# DI_DO.net
KiCad netlist of a schematic drawn in Altium Designer
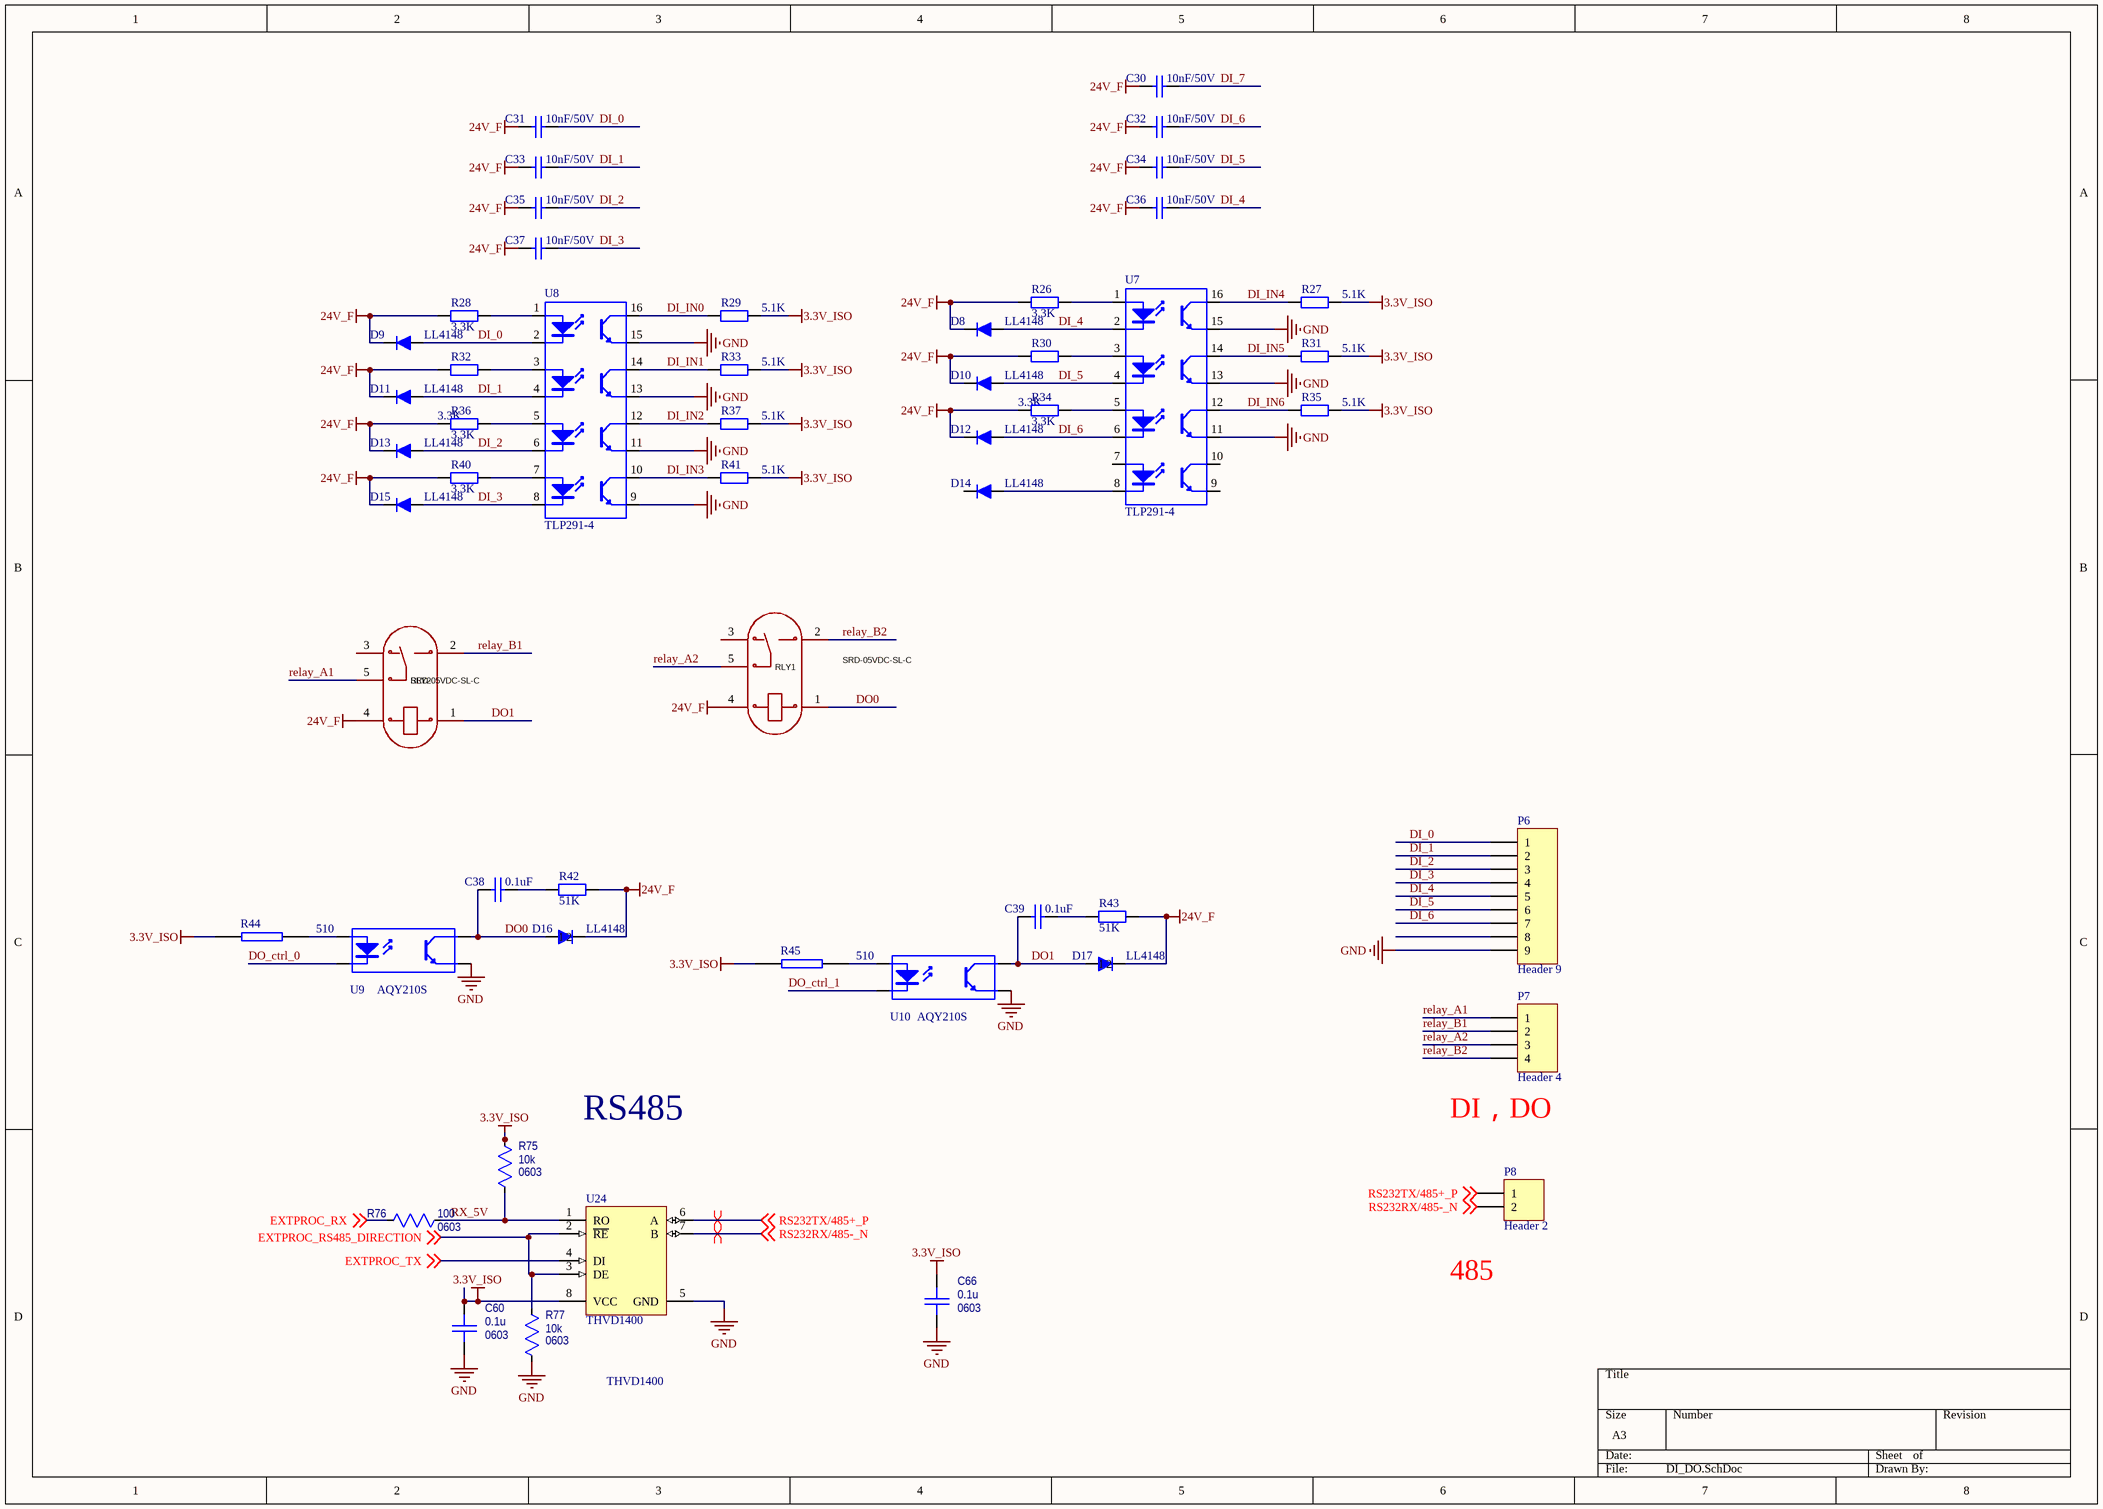
[diagram p0: DI_DO.SchDoc]

(export (version "E")
  (design (tool "Eeschema 10.0.6"))
  (components
    (comp (ref "C30")
      (value "10nF/50V")
      (footprint "0603C")
      (description "Capacitor")
      (fields (field (name "PUBLISHER") "Altium Limited"))
      (libsource (lib "Miscellaneous Devices") (part "Cap"))
    )
    (comp (ref "C31")
      (value "10nF/50V")
      (footprint "0603C")
      (description "Capacitor")
      (fields (field (name "PUBLISHER") "Altium Limited"))
      (libsource (lib "Miscellaneous Devices") (part "Cap"))
    )
    (comp (ref "C32")
      (value "10nF/50V")
      (footprint "0603C")
      (description "Capacitor")
      (fields (field (name "PUBLISHER") "Altium Limited"))
      (libsource (lib "Miscellaneous Devices") (part "Cap"))
    )
    (comp (ref "C33")
      (value "10nF/50V")
      (footprint "0603C")
      (description "Capacitor")
      (fields (field (name "PUBLISHER") "Altium Limited"))
      (libsource (lib "Miscellaneous Devices") (part "Cap"))
    )
    (comp (ref "C34")
      (value "10nF/50V")
      (footprint "0603C")
      (description "Capacitor")
      (fields (field (name "PUBLISHER") "Altium Limited"))
      (libsource (lib "Miscellaneous Devices") (part "Cap"))
    )
    (comp (ref "C35")
      (value "10nF/50V")
      (footprint "0603C")
      (description "Capacitor")
      (fields (field (name "PUBLISHER") "Altium Limited"))
      (libsource (lib "Miscellaneous Devices") (part "Cap"))
    )
    (comp (ref "C36")
      (value "10nF/50V")
      (footprint "0603C")
      (description "Capacitor")
      (fields (field (name "PUBLISHER") "Altium Limited"))
      (libsource (lib "Miscellaneous Devices") (part "Cap"))
    )
    (comp (ref "C37")
      (value "10nF/50V")
      (footprint "0603C")
      (description "Capacitor")
      (fields (field (name "PUBLISHER") "Altium Limited"))
      (libsource (lib "Miscellaneous Devices") (part "Cap"))
    )
    (comp (ref "C38")
      (value "0.1uF")
      (footprint "0603C")
      (description "Capacitor")
      (libsource (lib "*") (part "CAP"))
    )
    (comp (ref "C39")
      (value "0.1uF")
      (footprint "0603C")
      (description "Capacitor")
      (libsource (lib "*") (part "CAP"))
    )
    (comp (ref "C60")
      (value "0.1u")
      (footprint "CAPC1608X092N_0603")
      (description "Capacitor, MLCC")
      (fields
        (field (name "PARTNUMBER") "C0603C104M5RACTU")
        (field (name "TOLERANCE") "[tol]")
        (field (name "PACKAGE") "0603")
      )
      (libsource (lib "Karl") (part "Capacitor_0603"))
    )
    (comp (ref "C66")
      (value "0.1u")
      (footprint "CAPC1608X092N_0603")
      (description "Capacitor, MLCC")
      (fields
        (field (name "PARTNUMBER") "C0603C104M5RACTU")
        (field (name "TOLERANCE") "[tol]")
        (field (name "PACKAGE") "0603")
      )
      (libsource (lib "Karl") (part "Capacitor_0603"))
    )
    (comp (ref "D8")
      (value "LL4148")
      (footprint "DO-213AB/LL34/MiniMELF")
      (description "VISHAY,LL4148,圆柱体MiniMELF100V/2A,ROHS")
      (libsource (lib "Device2018") (part "LL4148"))
    )
    (comp (ref "D9")
      (value "LL4148")
      (footprint "DO-213AB/LL34/MiniMELF")
      (description "VISHAY,LL4148,圆柱体MiniMELF100V/2A,ROHS")
      (libsource (lib "Device2018") (part "LL4148"))
    )
    (comp (ref "D10")
      (value "LL4148")
      (footprint "DO-213AB/LL34/MiniMELF")
      (description "VISHAY,LL4148,圆柱体MiniMELF100V/2A,ROHS")
      (libsource (lib "Device2018") (part "LL4148"))
    )
    (comp (ref "D11")
      (value "LL4148")
      (footprint "DO-213AB/LL34/MiniMELF")
      (description "VISHAY,LL4148,圆柱体MiniMELF100V/2A,ROHS")
      (libsource (lib "Device2018") (part "LL4148"))
    )
    (comp (ref "D12")
      (value "LL4148")
      (footprint "DO-213AB/LL34/MiniMELF")
      (description "VISHAY,LL4148,圆柱体MiniMELF100V/2A,ROHS")
      (libsource (lib "Device2018") (part "LL4148"))
    )
    (comp (ref "D13")
      (value "LL4148")
      (footprint "DO-213AB/LL34/MiniMELF")
      (description "VISHAY,LL4148,圆柱体MiniMELF100V/2A,ROHS")
      (libsource (lib "Device2018") (part "LL4148"))
    )
    (comp (ref "D14")
      (value "LL4148")
      (footprint "DO-213AB/LL34/MiniMELF")
      (description "VISHAY,LL4148,圆柱体MiniMELF100V/2A,ROHS")
      (libsource (lib "Device2018") (part "LL4148"))
    )
    (comp (ref "D15")
      (value "LL4148")
      (footprint "DO-213AB/LL34/MiniMELF")
      (description "VISHAY,LL4148,圆柱体MiniMELF100V/2A,ROHS")
      (libsource (lib "Device2018") (part "LL4148"))
    )
    (comp (ref "D16")
      (value "LL4148")
      (footprint "DO-213AB/LL34/MiniMELF")
      (description "VISHAY,LL4148,圆柱体MiniMELF100V/2A,ROHS")
      (libsource (lib "") (part "LL4148_1"))
    )
    (comp (ref "D17")
      (value "LL4148")
      (footprint "DO-213AB/LL34/MiniMELF")
      (description "VISHAY,LL4148,圆柱体MiniMELF100V/2A,ROHS")
      (libsource (lib "") (part "LL4148_1"))
    )
    (comp (ref "P6")
      (value "Header 9")
      (footprint "HDR1X9")
      (description "Header, 9-Pin")
      (fields (field (name "PUBLISHER") "Altium Limited"))
      (libsource (lib "Miscellaneous Connectors") (part "Header 9"))
    )
    (comp (ref "P7")
      (value "Header 4")
      (footprint "HDR1X4")
      (description "Header, 4-Pin")
      (fields (field (name "PUBLISHER") "Altium Limited"))
      (libsource (lib "Miscellaneous Connectors") (part "Header 4"))
    )
    (comp (ref "P8")
      (value "Header 2")
      (footprint "HDR1X2")
      (description "Header, 2-Pin")
      (fields (field (name "PUBLISHER") "Altium Limited"))
      (libsource (lib "Miscellaneous Connectors") (part "Header 2"))
    )
    (comp (ref "R26") (value "3.3K") (footprint "0603R") (libsource (lib "MQlibrary") (part "Res0805M")))
    (comp (ref "R27") (value "5.1K") (footprint "0603R") (libsource (lib "MQlibrary") (part "Res0805M")))
    (comp (ref "R28") (value "3.3K") (footprint "0603R") (libsource (lib "MQlibrary") (part "Res0805M")))
    (comp (ref "R29") (value "5.1K") (footprint "0603R") (libsource (lib "MQlibrary") (part "Res0805M")))
    (comp (ref "R30") (value "3.3K") (footprint "0603R") (libsource (lib "MQlibrary") (part "Res0805M")))
    (comp (ref "R31") (value "5.1K") (footprint "0603R") (libsource (lib "MQlibrary") (part "Res0805M")))
    (comp (ref "R32") (value "3.3K") (footprint "0603R") (libsource (lib "MQlibrary") (part "Res0805M")))
    (comp (ref "R33") (value "5.1K") (footprint "0603R") (libsource (lib "MQlibrary") (part "Res0805M")))
    (comp (ref "R34") (value "3.3K") (footprint "0603R") (libsource (lib "MQlibrary") (part "Res0805M")))
    (comp (ref "R35") (value "5.1K") (footprint "0603R") (libsource (lib "MQlibrary") (part "Res0805M")))
    (comp (ref "R36") (value "3.3K") (footprint "0603R") (libsource (lib "MQlibrary") (part "Res0805M")))
    (comp (ref "R37") (value "5.1K") (footprint "0603R") (libsource (lib "MQlibrary") (part "Res0805M")))
    (comp (ref "R40") (value "3.3K") (footprint "0603R") (libsource (lib "MQlibrary") (part "Res0805M")))
    (comp (ref "R41") (value "5.1K") (footprint "0603R") (libsource (lib "MQlibrary") (part "Res0805M")))
    (comp (ref "R42") (value "51K") (footprint "0603R") (libsource (lib "") (part "Res0805M_1")))
    (comp (ref "R43") (value "51K") (footprint "0603R") (libsource (lib "") (part "Res0805M_1")))
    (comp (ref "R44") (value "510") (footprint "0603R") (libsource (lib "*") (part "RES2")))
    (comp (ref "R45") (value "510") (footprint "0603R") (libsource (lib "*") (part "RES2")))
    (comp (ref "R75")
      (value "10k")
      (footprint "RESC1608X055N_0603")
      (description "Resistor, Standard")
      (fields
        (field (name "PARTNUMBER") "RC0603FR-0710KL")
        (field (name "TOLERANCE") "tol")
        (field (name "PACKAGE") "0603")
      )
      (libsource (lib "Karl") (part "Resistor_0603"))
    )
    (comp (ref "R76")
      (value "100")
      (footprint "RESC1608X055N_0603")
      (description "Resistor, Standard")
      (fields
        (field (name "PARTNUMBER") "RC0603FR-07100RL")
        (field (name "TOLERANCE") "tol")
        (field (name "PACKAGE") "0603")
      )
      (libsource (lib "Karl") (part "Resistor_0603"))
    )
    (comp (ref "R77")
      (value "10k")
      (footprint "RESC1608X055N_0603")
      (description "Resistor, Standard")
      (fields
        (field (name "PARTNUMBER") "RC0603FR-0710KL")
        (field (name "TOLERANCE") "tol")
        (field (name "PACKAGE") "0603")
      )
      (libsource (lib "Karl") (part "Resistor_0603"))
    )
    (comp (ref "RLY1")
      (value "SRD-05VDC-SL-C")
      (footprint "RELAY-TH_SRD-XXVDC-XL-C")
      (fields (field (name "MANUFACTURER") "松乐"))
      (libsource (lib "altium-import") (part "root_0_SRD-05VDC-SL-C_"))
    )
    (comp (ref "RLY2")
      (value "SRD-05VDC-SL-C")
      (footprint "RELAY-TH_SRD-XXVDC-XL-C")
      (fields (field (name "MANUFACTURER") "松乐"))
      (libsource (lib "altium-import") (part "root_0_SRD-05VDC-SL-C_"))
    )
    (comp (ref "U7") (value "TLP291-4") (footprint "SOP16-T") (libsource (lib "DI16") (part "TLP281-4")))
    (comp (ref "U8") (value "TLP291-4") (footprint "SOP16-T") (libsource (lib "DI16") (part "TLP281-4")))
    (comp (ref "U9")
      (value "AQY210S")
      (footprint "sop4")
      (description "4-Pin Phototransistor Optocoupler")
      (fields (field (name "PUBLISHER") "Altium Limited"))
      (libsource (lib "Miscellaneous Devices") (part "Optoisolator1"))
    )
    (comp (ref "U10")
      (value "AQY210S")
      (footprint "sop4")
      (description "4-Pin Phototransistor Optocoupler")
      (fields (field (name "PUBLISHER") "Altium Limited"))
      (libsource (lib "Miscellaneous Devices") (part "Optoisolator1"))
    )
    (comp (ref "U24")
      (value "THVD1400")
      (footprint "MAXM-S8+4_M")
      (fields (field (name "PARTNUMBER") "MAX33071EASA+"))
      (libsource (lib "Bogen") (part "MAX33071EASA+"))
    )
  )
  (nets
    (net (code "1") (name "/DI_0") (class "Default")
      (node (ref "C31") (pin "2") (pinfunction "2_2") (pintype "passive"))
      (node (ref "D9") (pin "1") (pinfunction "2_1") (pintype "passive"))
      (node (ref "P6") (pin "1") (pinfunction "1_1") (pintype "passive"))
      (node (ref "U8") (pin "2") (pinfunction "K_2") (pintype "passive"))
    )
    (net (code "2") (name "/DI_1") (class "Default")
      (node (ref "C33") (pin "2") (pinfunction "2_2") (pintype "passive"))
      (node (ref "D11") (pin "1") (pinfunction "2_1") (pintype "passive"))
      (node (ref "P6") (pin "2") (pinfunction "2_2") (pintype "passive"))
      (node (ref "U8") (pin "4") (pinfunction "K_4") (pintype "passive"))
    )
    (net (code "3") (name "/DI_2") (class "Default")
      (node (ref "C35") (pin "2") (pinfunction "2_2") (pintype "passive"))
      (node (ref "D13") (pin "1") (pinfunction "2_1") (pintype "passive"))
      (node (ref "P6") (pin "3") (pinfunction "3_3") (pintype "passive"))
      (node (ref "U8") (pin "6") (pinfunction "K_6") (pintype "passive"))
    )
    (net (code "4") (name "/DI_3") (class "Default")
      (node (ref "C37") (pin "2") (pinfunction "2_2") (pintype "passive"))
      (node (ref "D15") (pin "1") (pinfunction "2_1") (pintype "passive"))
      (node (ref "P6") (pin "4") (pinfunction "4_4") (pintype "passive"))
      (node (ref "U8") (pin "8") (pinfunction "K_8") (pintype "passive"))
    )
    (net (code "5") (name "/DI_4") (class "Default")
      (node (ref "C36") (pin "2") (pinfunction "2_2") (pintype "passive"))
      (node (ref "D8") (pin "1") (pinfunction "2_1") (pintype "passive"))
      (node (ref "P6") (pin "5") (pinfunction "5_5") (pintype "passive"))
      (node (ref "U7") (pin "2") (pinfunction "K_2") (pintype "passive"))
    )
    (net (code "6") (name "/DI_5") (class "Default")
      (node (ref "C34") (pin "2") (pinfunction "2_2") (pintype "passive"))
      (node (ref "D10") (pin "1") (pinfunction "2_1") (pintype "passive"))
      (node (ref "P6") (pin "6") (pinfunction "6_6") (pintype "passive"))
      (node (ref "U7") (pin "4") (pinfunction "K_4") (pintype "passive"))
    )
    (net (code "7") (name "/DI_6") (class "Default")
      (node (ref "C32") (pin "2") (pinfunction "2_2") (pintype "passive"))
      (node (ref "D12") (pin "1") (pinfunction "2_1") (pintype "passive"))
      (node (ref "P6") (pin "7") (pinfunction "7_7") (pintype "passive"))
      (node (ref "U7") (pin "6") (pinfunction "K_6") (pintype "passive"))
    )
    (net (code "8") (name "/DI_7") (class "Default")
      (node (ref "C30") (pin "2") (pinfunction "2_2") (pintype "passive"))
    )
    (net (code "9") (name "/DI_IN0") (class "Default")
      (node (ref "R29") (pin "2") (pinfunction "2_2") (pintype "passive"))
      (node (ref "U8") (pin "16") (pinfunction "C_16") (pintype "passive"))
    )
    (net (code "10") (name "/DI_IN1") (class "Default")
      (node (ref "R33") (pin "2") (pinfunction "2_2") (pintype "passive"))
      (node (ref "U8") (pin "14") (pinfunction "C_14") (pintype "passive"))
    )
    (net (code "11") (name "/DI_IN2") (class "Default")
      (node (ref "R37") (pin "2") (pinfunction "2_2") (pintype "passive"))
      (node (ref "U8") (pin "12") (pinfunction "C_12") (pintype "passive"))
    )
    (net (code "12") (name "/DI_IN3") (class "Default")
      (node (ref "R41") (pin "2") (pinfunction "2_2") (pintype "passive"))
      (node (ref "U8") (pin "10") (pinfunction "C_10") (pintype "passive"))
    )
    (net (code "13") (name "/DI_IN4") (class "Default")
      (node (ref "R27") (pin "2") (pinfunction "2_2") (pintype "passive"))
      (node (ref "U7") (pin "16") (pinfunction "C_16") (pintype "passive"))
    )
    (net (code "14") (name "/DI_IN5") (class "Default")
      (node (ref "R31") (pin "2") (pinfunction "2_2") (pintype "passive"))
      (node (ref "U7") (pin "14") (pinfunction "C_14") (pintype "passive"))
    )
    (net (code "15") (name "/DI_IN6") (class "Default")
      (node (ref "R35") (pin "2") (pinfunction "2_2") (pintype "passive"))
      (node (ref "U7") (pin "12") (pinfunction "C_12") (pintype "passive"))
    )
    (net (code "16") (name "/DO0") (class "Default")
      (node (ref "C38") (pin "1") (pinfunction "1_1") (pintype "passive"))
      (node (ref "D16") (pin "1") (pinfunction "2_1") (pintype "passive"))
      (node (ref "RLY1") (pin "1") (pinfunction "1_1") (pintype "passive"))
      (node (ref "U9") (pin "4") (pinfunction "C_4") (pintype "passive"))
    )
    (net (code "17") (name "/DO1") (class "Default")
      (node (ref "C39") (pin "1") (pinfunction "1_1") (pintype "passive"))
      (node (ref "D17") (pin "1") (pinfunction "2_1") (pintype "passive"))
      (node (ref "RLY2") (pin "1") (pinfunction "1_1") (pintype "passive"))
      (node (ref "U10") (pin "4") (pinfunction "C_4") (pintype "passive"))
    )
    (net (code "18") (name "/DO_ctrl_0") (class "Default")
      (node (ref "U9") (pin "2") (pinfunction "K_2") (pintype "passive"))
    )
    (net (code "19") (name "/DO_ctrl_1") (class "Default")
      (node (ref "U10") (pin "2") (pinfunction "K_2") (pintype "passive"))
    )
    (net (code "20") (name "/RX_5V") (class "Default")
      (node (ref "R75") (pin "1") (pinfunction "1_1") (pintype "passive"))
      (node (ref "R76") (pin "1") (pinfunction "1_1") (pintype "passive"))
      (node (ref "U24") (pin "1") (pinfunction "RO_1") (pintype "tri_state"))
    )
    (net (code "21") (name "/relay_A1") (class "Default")
      (node (ref "P7") (pin "1") (pinfunction "1_1") (pintype "passive"))
      (node (ref "RLY2") (pin "5") (pinfunction "5_5") (pintype "passive"))
    )
    (net (code "22") (name "/relay_A2") (class "Default")
      (node (ref "P7") (pin "3") (pinfunction "3_3") (pintype "passive"))
      (node (ref "RLY1") (pin "5") (pinfunction "5_5") (pintype "passive"))
    )
    (net (code "23") (name "/relay_B1") (class "Default")
      (node (ref "P7") (pin "2") (pinfunction "2_2") (pintype "passive"))
      (node (ref "RLY2") (pin "2") (pinfunction "2_2") (pintype "passive"))
    )
    (net (code "24") (name "/relay_B2") (class "Default")
      (node (ref "P7") (pin "4") (pinfunction "4_4") (pintype "passive"))
      (node (ref "RLY1") (pin "2") (pinfunction "2_2") (pintype "passive"))
    )
    (net (code "25") (name "3.3V_ISO") (class "Default")
      (node (ref "C60") (pin "1") (pinfunction "1_1") (pintype "passive"))
      (node (ref "C66") (pin "1") (pinfunction "1_1") (pintype "passive"))
      (node (ref "R27") (pin "1") (pinfunction "1_1") (pintype "passive"))
      (node (ref "R29") (pin "1") (pinfunction "1_1") (pintype "passive"))
      (node (ref "R31") (pin "1") (pinfunction "1_1") (pintype "passive"))
      (node (ref "R33") (pin "1") (pinfunction "1_1") (pintype "passive"))
      (node (ref "R35") (pin "1") (pinfunction "1_1") (pintype "passive"))
      (node (ref "R37") (pin "1") (pinfunction "1_1") (pintype "passive"))
      (node (ref "R41") (pin "1") (pinfunction "1_1") (pintype "passive"))
      (node (ref "R44") (pin "2") (pinfunction "2_2") (pintype "passive"))
      (node (ref "R45") (pin "2") (pinfunction "2_2") (pintype "passive"))
      (node (ref "R75") (pin "2") (pinfunction "2_2") (pintype "passive"))
      (node (ref "U24") (pin "8") (pinfunction "VCC_8") (pintype "power_in"))
    )
    (net (code "26") (name "24V_F") (class "Default")
      (node (ref "C30") (pin "1") (pinfunction "1_1") (pintype "passive"))
      (node (ref "C31") (pin "1") (pinfunction "1_1") (pintype "passive"))
      (node (ref "C32") (pin "1") (pinfunction "1_1") (pintype "passive"))
      (node (ref "C33") (pin "1") (pinfunction "1_1") (pintype "passive"))
      (node (ref "C34") (pin "1") (pinfunction "1_1") (pintype "passive"))
      (node (ref "C35") (pin "1") (pinfunction "1_1") (pintype "passive"))
      (node (ref "C36") (pin "1") (pinfunction "1_1") (pintype "passive"))
      (node (ref "C37") (pin "1") (pinfunction "1_1") (pintype "passive"))
      (node (ref "D10") (pin "2") (pinfunction "1_2") (pintype "passive"))
      (node (ref "D11") (pin "2") (pinfunction "1_2") (pintype "passive"))
      (node (ref "D12") (pin "2") (pinfunction "1_2") (pintype "passive"))
      (node (ref "D13") (pin "2") (pinfunction "1_2") (pintype "passive"))
      (node (ref "D15") (pin "2") (pinfunction "1_2") (pintype "passive"))
      (node (ref "D16") (pin "2") (pinfunction "1_2") (pintype "passive"))
      (node (ref "D17") (pin "2") (pinfunction "1_2") (pintype "passive"))
      (node (ref "D8") (pin "2") (pinfunction "1_2") (pintype "passive"))
      (node (ref "D9") (pin "2") (pinfunction "1_2") (pintype "passive"))
      (node (ref "R26") (pin "2") (pinfunction "2_2") (pintype "passive"))
      (node (ref "R28") (pin "2") (pinfunction "2_2") (pintype "passive"))
      (node (ref "R30") (pin "2") (pinfunction "2_2") (pintype "passive"))
      (node (ref "R32") (pin "2") (pinfunction "2_2") (pintype "passive"))
      (node (ref "R34") (pin "2") (pinfunction "2_2") (pintype "passive"))
      (node (ref "R36") (pin "2") (pinfunction "2_2") (pintype "passive"))
      (node (ref "R40") (pin "2") (pinfunction "2_2") (pintype "passive"))
      (node (ref "R42") (pin "2") (pinfunction "2_2") (pintype "passive"))
      (node (ref "R43") (pin "2") (pinfunction "2_2") (pintype "passive"))
      (node (ref "RLY1") (pin "4") (pinfunction "4_4") (pintype "passive"))
      (node (ref "RLY2") (pin "4") (pinfunction "4_4") (pintype "passive"))
    )
    (net (code "27") (name "EXTPROC_RS485_DIRECTION") (class "Default")
      (node (ref "R77") (pin "2") (pinfunction "2_2") (pintype "passive"))
      (node (ref "U24") (pin "2") (pinfunction "~{RE}_2") (pintype "input"))
      (node (ref "U24") (pin "3") (pinfunction "DE_3") (pintype "input"))
    )
    (net (code "28") (name "EXTPROC_RX") (class "Default")
      (node (ref "R76") (pin "2") (pinfunction "2_2") (pintype "passive"))
    )
    (net (code "29") (name "EXTPROC_TX") (class "Default")
      (node (ref "U24") (pin "4") (pinfunction "DI_4") (pintype "input"))
    )
    (net (code "30") (name "GND") (class "Default")
      (node (ref "C60") (pin "2") (pinfunction "2_2") (pintype "passive"))
      (node (ref "C66") (pin "2") (pinfunction "2_2") (pintype "passive"))
      (node (ref "P6") (pin "9") (pinfunction "9_9") (pintype "passive"))
      (node (ref "R77") (pin "1") (pinfunction "1_1") (pintype "passive"))
      (node (ref "U10") (pin "3") (pinfunction "E_3") (pintype "passive"))
      (node (ref "U24") (pin "5") (pinfunction "GND_5") (pintype "power_in"))
      (node (ref "U7") (pin "11") (pinfunction "E_11") (pintype "passive"))
      (node (ref "U7") (pin "13") (pinfunction "E_13") (pintype "passive"))
      (node (ref "U7") (pin "15") (pinfunction "E_15") (pintype "passive"))
      (node (ref "U8") (pin "11") (pinfunction "E_11") (pintype "passive"))
      (node (ref "U8") (pin "13") (pinfunction "E_13") (pintype "passive"))
      (node (ref "U8") (pin "15") (pinfunction "E_15") (pintype "passive"))
      (node (ref "U8") (pin "9") (pinfunction "E_9") (pintype "passive"))
      (node (ref "U9") (pin "3") (pinfunction "E_3") (pintype "passive"))
    )
    (net (code "31") (name "Net-(C38-Pad2)") (class "Default")
      (node (ref "C38") (pin "2") (pinfunction "2_2") (pintype "passive"))
      (node (ref "R42") (pin "1") (pinfunction "1_1") (pintype "passive"))
    )
    (net (code "32") (name "Net-(C39-Pad2)") (class "Default")
      (node (ref "C39") (pin "2") (pinfunction "2_2") (pintype "passive"))
      (node (ref "R43") (pin "1") (pinfunction "1_1") (pintype "passive"))
    )
    (net (code "33") (name "Net-(D14-2)") (class "Default")
      (node (ref "D14") (pin "1") (pinfunction "2_1") (pintype "passive"))
      (node (ref "U7") (pin "8") (pinfunction "K_8") (pintype "passive"))
    )
    (net (code "34") (name "Net-(R26-Pad1)") (class "Default")
      (node (ref "R26") (pin "1") (pinfunction "1_1") (pintype "passive"))
      (node (ref "U7") (pin "1") (pinfunction "A_1") (pintype "passive"))
    )
    (net (code "35") (name "Net-(R28-Pad1)") (class "Default")
      (node (ref "R28") (pin "1") (pinfunction "1_1") (pintype "passive"))
      (node (ref "U8") (pin "1") (pinfunction "A_1") (pintype "passive"))
    )
    (net (code "36") (name "Net-(R30-Pad1)") (class "Default")
      (node (ref "R30") (pin "1") (pinfunction "1_1") (pintype "passive"))
      (node (ref "U7") (pin "3") (pinfunction "A_3") (pintype "passive"))
    )
    (net (code "37") (name "Net-(R32-Pad1)") (class "Default")
      (node (ref "R32") (pin "1") (pinfunction "1_1") (pintype "passive"))
      (node (ref "U8") (pin "3") (pinfunction "A_3") (pintype "passive"))
    )
    (net (code "38") (name "Net-(R34-Pad1)") (class "Default")
      (node (ref "R34") (pin "1") (pinfunction "1_1") (pintype "passive"))
      (node (ref "U7") (pin "5") (pinfunction "A_5") (pintype "passive"))
    )
    (net (code "39") (name "Net-(R36-Pad1)") (class "Default")
      (node (ref "R36") (pin "1") (pinfunction "1_1") (pintype "passive"))
      (node (ref "U8") (pin "5") (pinfunction "A_5") (pintype "passive"))
    )
    (net (code "40") (name "Net-(R40-Pad1)") (class "Default")
      (node (ref "R40") (pin "1") (pinfunction "1_1") (pintype "passive"))
      (node (ref "U8") (pin "7") (pinfunction "A_7") (pintype "passive"))
    )
    (net (code "41") (name "Net-(U9-A)") (class "Default")
      (node (ref "R44") (pin "1") (pinfunction "1_1") (pintype "passive"))
      (node (ref "U9") (pin "1") (pinfunction "A_1") (pintype "passive"))
    )
    (net (code "42") (name "Net-(U10-A)") (class "Default")
      (node (ref "R45") (pin "1") (pinfunction "1_1") (pintype "passive"))
      (node (ref "U10") (pin "1") (pinfunction "A_1") (pintype "passive"))
    )
    (net (code "43") (name "RS232RX{slash}485-_N") (class "Default")
      (node (ref "P8") (pin "2") (pinfunction "2_2") (pintype "passive"))
      (node (ref "U24") (pin "7") (pinfunction "B_7") (pintype "bidirectional"))
    )
    (net (code "44") (name "RS232TX{slash}485+_P") (class "Default")
      (node (ref "P8") (pin "1") (pinfunction "1_1") (pintype "passive"))
      (node (ref "U24") (pin "6") (pinfunction "A_6") (pintype "bidirectional"))
    )
    (net (code "45") (name "unconnected-(D14-1-Pad2)") (class "Default")
      (node (ref "D14") (pin "2") (pinfunction "1_2") (pintype "passive"))
    )
    (net (code "46") (name "unconnected-(P6-Pad8)") (class "Default")
      (node (ref "P6") (pin "8") (pinfunction "8_8") (pintype "passive"))
    )
    (net (code "47") (name "unconnected-(RLY1-Pad3)") (class "Default")
      (node (ref "RLY1") (pin "3") (pinfunction "3_3") (pintype "passive"))
    )
    (net (code "48") (name "unconnected-(RLY2-Pad3)") (class "Default")
      (node (ref "RLY2") (pin "3") (pinfunction "3_3") (pintype "passive"))
    )
    (net (code "49") (name "unconnected-(U7-A-Pad7)") (class "Default")
      (node (ref "U7") (pin "7") (pinfunction "A_7") (pintype "passive"))
    )
    (net (code "50") (name "unconnected-(U7-C-Pad10)") (class "Default")
      (node (ref "U7") (pin "10") (pinfunction "C_10") (pintype "passive"))
    )
    (net (code "51") (name "unconnected-(U7-E-Pad9)") (class "Default")
      (node (ref "U7") (pin "9") (pinfunction "E_9") (pintype "passive"))
    )
  )
)
